# 1_47_LCD.net
KiCad netlist of a schematic drawn in Altium Designer
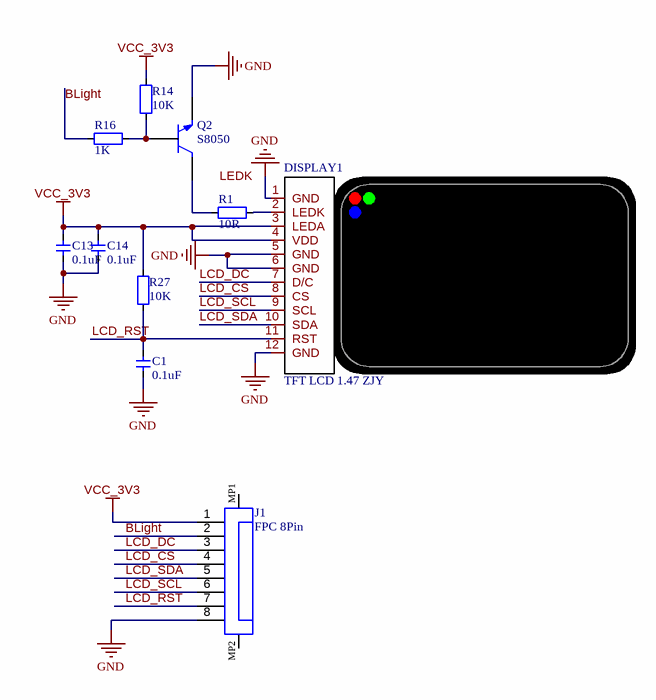
[diagram p0: 1.47 LCD .SchDoc]

(export (version "E")
  (design (tool "Eeschema 10.0.6"))
  (components
    (comp (ref "C1")
      (value "0.1uF")
      (footprint "CAP_0402")
      (description "Capacitor")
      (libsource (lib "Common") (part "电容-0402"))
    )
    (comp (ref "C13")
      (value "0.1uF")
      (footprint "CAP_0402")
      (description "Capacitor")
      (libsource (lib "Common") (part "电容-0402"))
    )
    (comp (ref "C14")
      (value "0.1uF")
      (footprint "CAP_0402")
      (description "Capacitor")
      (libsource (lib "Common") (part "电容-0402"))
    )
    (comp (ref "DISPLAY1")
      (value "TFT LCD 1.47 ZJY")
      (footprint "ZJY 1.47‘’ TFT LCD")
      (description "中景园1.47屏幕")
      (libsource (lib "Common") (part "TFT LCD 1.47 ZJY"))
    )
    (comp (ref "J1")
      (value "FPC 8Pin")
      (footprint "FPC 0.5MM 8P 1.0H")
      (libsource (lib "Common") (part "FPC 8Pin"))
    )
    (comp (ref "Q2")
      (value "S8050")
      (footprint "SOT23-3")
      (description "NPN")
      (libsource (lib "common_schlib") (part "S8050"))
    )
    (comp (ref "R1")
      (value "10R")
      (footprint "RES_0402")
      (description "Resistor")
      (libsource (lib "") (part "电阻-0402_1"))
    )
    (comp (ref "R14")
      (value "10K")
      (footprint "RES_0402")
      (description "Resistor")
      (libsource (lib "") (part "电阻-0402_2"))
    )
    (comp (ref "R16")
      (value "1K")
      (footprint "RES_0402")
      (description "Resistor")
      (libsource (lib "") (part "电阻-0402_1"))
    )
    (comp (ref "R27")
      (value "10K")
      (footprint "RES_0402")
      (description "Resistor")
      (libsource (lib "common_schlib") (part "电阻-0402"))
    )
  )
  (nets
    (net (code "1") (name "/BLight") (class "Default")
      (node (ref "J1") (pin "2") (pinfunction "2_2") (pintype "passive"))
      (node (ref "R16") (pin "1") (pinfunction "1_1") (pintype "passive"))
    )
    (net (code "2") (name "/LCD_CS") (class "Default")
      (node (ref "DISPLAY1") (pin "8") (pinfunction "CS_8") (pintype "passive"))
      (node (ref "J1") (pin "4") (pinfunction "4_4") (pintype "passive"))
    )
    (net (code "3") (name "/LCD_DC") (class "Default")
      (node (ref "DISPLAY1") (pin "7") (pinfunction "D/C_7") (pintype "passive"))
      (node (ref "J1") (pin "3") (pinfunction "3_3") (pintype "passive"))
    )
    (net (code "4") (name "/LCD_RST") (class "Default")
      (node (ref "C1") (pin "2") (pinfunction "2_2") (pintype "passive"))
      (node (ref "DISPLAY1") (pin "11") (pinfunction "RST_11") (pintype "passive"))
      (node (ref "J1") (pin "7") (pinfunction "7_7") (pintype "passive"))
      (node (ref "R27") (pin "1") (pinfunction "1_1") (pintype "passive"))
    )
    (net (code "5") (name "/LCD_SCL") (class "Default")
      (node (ref "DISPLAY1") (pin "9") (pinfunction "SCL_9") (pintype "passive"))
      (node (ref "J1") (pin "6") (pinfunction "6_6") (pintype "passive"))
    )
    (net (code "6") (name "/LCD_SDA") (class "Default")
      (node (ref "DISPLAY1") (pin "10") (pinfunction "SDA_10") (pintype "passive"))
      (node (ref "J1") (pin "5") (pinfunction "5_5") (pintype "passive"))
    )
    (net (code "8") (name "GND") (class "Default")
      (node (ref "C1") (pin "1") (pinfunction "1_1") (pintype "passive"))
      (node (ref "C13") (pin "1") (pinfunction "1_1") (pintype "passive"))
      (node (ref "C14") (pin "1") (pinfunction "1_1") (pintype "passive"))
      (node (ref "DISPLAY1") (pin "1") (pinfunction "GND_1") (pintype "passive"))
      (node (ref "DISPLAY1") (pin "12") (pinfunction "GND_12") (pintype "passive"))
      (node (ref "DISPLAY1") (pin "5") (pinfunction "GND_5") (pintype "passive"))
      (node (ref "DISPLAY1") (pin "6") (pinfunction "GND_6") (pintype "passive"))
      (node (ref "J1") (pin "8") (pinfunction "8_8") (pintype "passive"))
      (node (ref "Q2") (pin "2") (pinfunction "E_2") (pintype "passive"))
    )
    (net (code "9") (name "Net-(DISPLAY1-LEDK)") (class "Default")
      (node (ref "DISPLAY1") (pin "2") (pinfunction "LEDK_2") (pintype "passive"))
      (node (ref "R1") (pin "2") (pinfunction "2_2") (pintype "passive"))
    )
    (net (code "10") (name "Net-(Q2-B)") (class "Default")
      (node (ref "Q2") (pin "1") (pinfunction "B_1") (pintype "passive"))
      (node (ref "R14") (pin "2") (pinfunction "2_2") (pintype "passive"))
      (node (ref "R16") (pin "2") (pinfunction "2_2") (pintype "passive"))
    )
    (net (code "11") (name "Net-(Q2-C)") (class "Default")
      (node (ref "Q2") (pin "3") (pinfunction "C_3") (pintype "passive"))
      (node (ref "R1") (pin "1") (pinfunction "1_1") (pintype "passive"))
    )
    (net (code "12") (name "VCC_3V3") (class "Default")
      (node (ref "C13") (pin "2") (pinfunction "2_2") (pintype "passive"))
      (node (ref "C14") (pin "2") (pinfunction "2_2") (pintype "passive"))
      (node (ref "DISPLAY1") (pin "3") (pinfunction "LEDA_3") (pintype "passive"))
      (node (ref "DISPLAY1") (pin "4") (pinfunction "VDD_4") (pintype "passive"))
      (node (ref "J1") (pin "1") (pinfunction "1_1") (pintype "passive"))
      (node (ref "R14") (pin "1") (pinfunction "1_1") (pintype "passive"))
      (node (ref "R27") (pin "2") (pinfunction "2_2") (pintype "passive"))
    )
    (net (code "13") (name "unconnected-(J1-PadMP1)") (class "Default")
      (node (ref "J1") (pin "MP1") (pinfunction "MP1_MP1") (pintype "passive"))
    )
    (net (code "14") (name "unconnected-(J1-PadMP2)") (class "Default")
      (node (ref "J1") (pin "MP2") (pinfunction "MP2_MP2") (pintype "passive"))
    )
  )
)
